# SCH_kea.net
KiCad netlist of a schematic drawn in EasyEDA
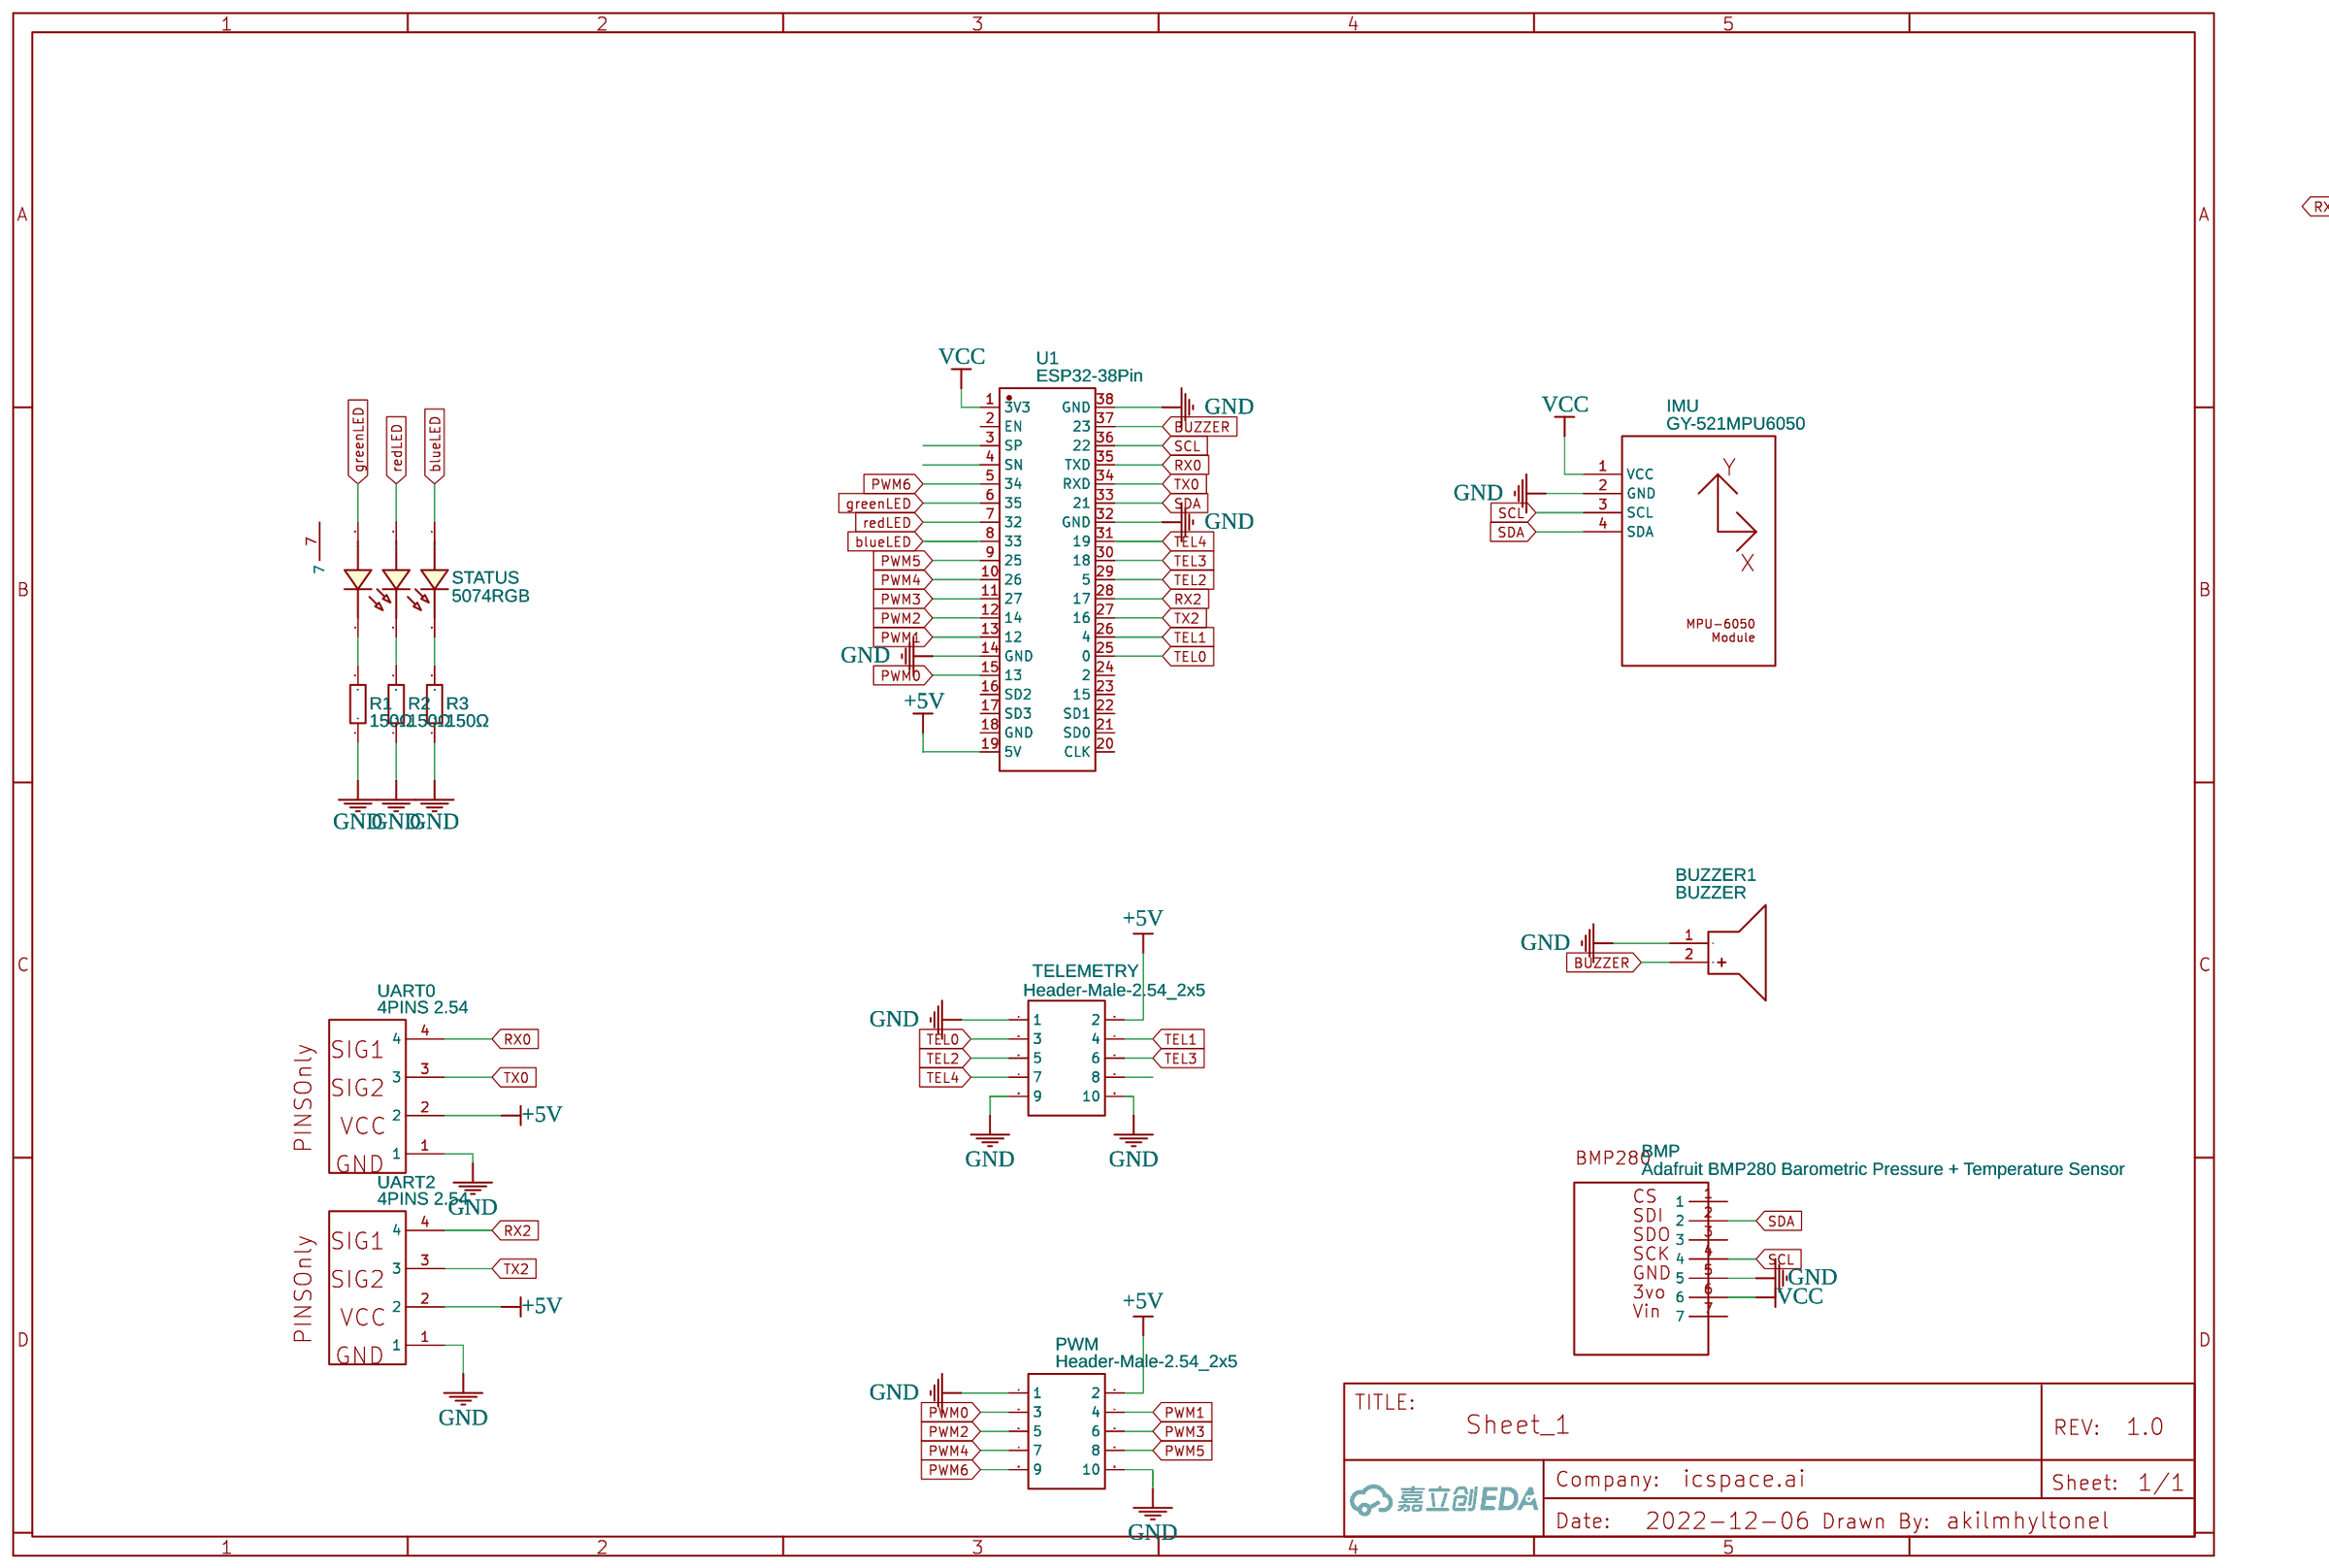
[diagram p0: schematic sheet]

(export (version "E")
  (design (tool "Eeschema 10.0.6"))
  (components
    (comp (ref "BMP")
      (value "Adafruit BMP280 Barometric Pressure + Temperature Sensor")
      (fields (field (name "BOM_Manufacturer Part") "Adafruit"))
      (libsource (lib "") (part "Adafruit BMP280 Barometric Pressure + Temperature Sensor"))
    )
    (comp (ref "BUZZER1")
      (value "BUZZER")
      (fields
        (field (name "BOM_Manufacturer Part") "buzzer")
        (field (name "BOM_Supplier Part") "C9900014030")
      )
      (libsource (lib "") (part "BUZZER"))
    )
    (comp (ref "IMU") (value "GY-521MPU6050") (libsource (lib "") (part "GY-521MPU6050")))
    (comp (ref "PWM")
      (value "Header-Male-2.54_2x5")
      (fields
        (field (name "BOM_Manufacturer Part") "2*5pHeaders  Pins 2.54mm")
        (field (name "BOM_Supplier Part") "C28207")
      )
      (libsource (lib "") (part "Header-Male-2.54_2x5"))
    )
    (comp (ref "R1")
      (value "150Ω")
      (fields
        (field (name "BOM_Manufacturer Part") "AECR0603F160KK9")
        (field (name "BOM_Supplier Part") "C352365")
      )
      (libsource (lib "") (part "AECR0603F160KK9"))
    )
    (comp (ref "R2")
      (value "150Ω")
      (fields
        (field (name "BOM_Manufacturer Part") "AECR0603F160KK9")
        (field (name "BOM_Supplier Part") "C352365")
      )
      (libsource (lib "") (part "AECR0603F160KK9"))
    )
    (comp (ref "R3")
      (value "150Ω")
      (fields
        (field (name "BOM_Manufacturer Part") "AECR0603F160KK9")
        (field (name "BOM_Supplier Part") "C352365")
      )
      (libsource (lib "") (part "AECR0603F160KK9"))
    )
    (comp (ref "STATUS")
      (value "5074RGB")
      (fields (field (name "BOM_Supplier Part") "C9900017134"))
      (libsource (lib "") (part "5074RGB"))
    )
    (comp (ref "TELEMETRY")
      (value "Header-Male-2.54_2x5")
      (fields
        (field (name "BOM_Manufacturer Part") "2*5pHeaders  Pins 2.54mm")
        (field (name "BOM_Supplier Part") "C28207")
      )
      (libsource (lib "") (part "Header-Male-2.54_2x5_1"))
    )
    (comp (ref "U1") (value "ESP32-38Pin") (libsource (lib "") (part "ESP32-38Pin")))
    (comp (ref "UART0") (value "4PINS 2.54") (libsource (lib "") (part "4PINS 2.54")))
    (comp (ref "UART2") (value "4PINS 2.54") (libsource (lib "") (part "4PINS 2.54")))
  )
  (nets
    (net (code "1") (name "+5V") (class "Default")
      (node (ref "PWM") (pin "2") (pinfunction "2_2") (pintype "input"))
      (node (ref "TELEMETRY") (pin "2") (pinfunction "2_2") (pintype "input"))
      (node (ref "U1") (pin "19") (pinfunction "5V_19") (pintype "unspecified"))
      (node (ref "UART0") (pin "2") (pinfunction "2_2") (pintype "unspecified"))
      (node (ref "UART2") (pin "2") (pinfunction "2_2") (pintype "unspecified"))
    )
    (net (code "2") (name "BUZZER") (class "Default")
      (node (ref "BUZZER1") (pin "2") (pinfunction "+_2") (pintype "unspecified"))
      (node (ref "U1") (pin "37") (pinfunction "23_37") (pintype "unspecified"))
    )
    (net (code "3") (name "GND") (class "Default")
      (node (ref "BMP") (pin "5") (pinfunction "5_5") (pintype "unspecified"))
      (node (ref "BUZZER1") (pin "1") (pinfunction "-_1") (pintype "unspecified"))
      (node (ref "IMU") (pin "2") (pinfunction "GND_2") (pintype "unspecified"))
      (node (ref "PWM") (pin "1") (pinfunction "1_1") (pintype "input"))
      (node (ref "PWM") (pin "10") (pinfunction "10_10") (pintype "input"))
      (node (ref "R1") (pin "1") (pinfunction "1_1") (pintype "unspecified"))
      (node (ref "R2") (pin "1") (pinfunction "1_1") (pintype "unspecified"))
      (node (ref "R3") (pin "1") (pinfunction "1_1") (pintype "unspecified"))
      (node (ref "TELEMETRY") (pin "1") (pinfunction "1_1") (pintype "input"))
      (node (ref "TELEMETRY") (pin "10") (pinfunction "10_10") (pintype "input"))
      (node (ref "TELEMETRY") (pin "9") (pinfunction "9_9") (pintype "input"))
      (node (ref "U1") (pin "14") (pinfunction "GND_14") (pintype "unspecified"))
      (node (ref "U1") (pin "32") (pinfunction "GND_32") (pintype "unspecified"))
      (node (ref "U1") (pin "38") (pinfunction "GND_38") (pintype "unspecified"))
      (node (ref "UART0") (pin "1") (pinfunction "1_1") (pintype "unspecified"))
      (node (ref "UART2") (pin "1") (pinfunction "1_1") (pintype "unspecified"))
    )
    (net (code "4") (name "Net-(R1-Pad2)") (class "Default")
      (node (ref "R1") (pin "2") (pinfunction "2_2") (pintype "unspecified"))
      (node (ref "STATUS") (pin "3") (pinfunction "-_3") (pintype "unspecified"))
    )
    (net (code "5") (name "Net-(R2-Pad2)") (class "Default")
      (node (ref "R2") (pin "2") (pinfunction "2_2") (pintype "unspecified"))
      (node (ref "STATUS") (pin "2") (pinfunction "-_2") (pintype "unspecified"))
    )
    (net (code "6") (name "Net-(R3-Pad2)") (class "Default")
      (node (ref "R3") (pin "2") (pinfunction "2_2") (pintype "unspecified"))
      (node (ref "STATUS") (pin "1") (pinfunction "-_1") (pintype "unspecified"))
    )
    (net (code "7") (name "PWM0") (class "Default")
      (node (ref "PWM") (pin "3") (pinfunction "3_3") (pintype "input"))
      (node (ref "U1") (pin "15") (pinfunction "13_15") (pintype "unspecified"))
    )
    (net (code "8") (name "PWM1") (class "Default")
      (node (ref "PWM") (pin "4") (pinfunction "4_4") (pintype "input"))
      (node (ref "U1") (pin "13") (pinfunction "12_13") (pintype "unspecified"))
    )
    (net (code "9") (name "PWM2") (class "Default")
      (node (ref "PWM") (pin "5") (pinfunction "5_5") (pintype "input"))
      (node (ref "U1") (pin "12") (pinfunction "14_12") (pintype "unspecified"))
    )
    (net (code "10") (name "PWM3") (class "Default")
      (node (ref "PWM") (pin "6") (pinfunction "6_6") (pintype "input"))
      (node (ref "U1") (pin "11") (pinfunction "27_11") (pintype "unspecified"))
    )
    (net (code "11") (name "PWM4") (class "Default")
      (node (ref "PWM") (pin "7") (pinfunction "7_7") (pintype "input"))
      (node (ref "U1") (pin "10") (pinfunction "26_10") (pintype "unspecified"))
    )
    (net (code "12") (name "PWM5") (class "Default")
      (node (ref "PWM") (pin "8") (pinfunction "8_8") (pintype "input"))
      (node (ref "U1") (pin "9") (pinfunction "25_9") (pintype "unspecified"))
    )
    (net (code "13") (name "PWM6") (class "Default")
      (node (ref "PWM") (pin "9") (pinfunction "9_9") (pintype "input"))
      (node (ref "U1") (pin "5") (pinfunction "34_5") (pintype "unspecified"))
    )
    (net (code "14") (name "RX0") (class "Default")
      (node (ref "U1") (pin "35") (pinfunction "TXD_35") (pintype "unspecified"))
      (node (ref "UART0") (pin "4") (pinfunction "4_4") (pintype "unspecified"))
    )
    (net (code "15") (name "RX2") (class "Default")
      (node (ref "U1") (pin "28") (pinfunction "17_28") (pintype "unspecified"))
      (node (ref "UART2") (pin "4") (pinfunction "4_4") (pintype "unspecified"))
    )
    (net (code "16") (name "SCL") (class "Default")
      (node (ref "BMP") (pin "4") (pinfunction "4_4") (pintype "unspecified"))
      (node (ref "IMU") (pin "3") (pinfunction "SCL_3") (pintype "unspecified"))
      (node (ref "U1") (pin "36") (pinfunction "22_36") (pintype "unspecified"))
    )
    (net (code "17") (name "SDA") (class "Default")
      (node (ref "BMP") (pin "2") (pinfunction "2_2") (pintype "unspecified"))
      (node (ref "IMU") (pin "4") (pinfunction "SDA_4") (pintype "unspecified"))
      (node (ref "U1") (pin "33") (pinfunction "21_33") (pintype "unspecified"))
    )
    (net (code "18") (name "TEL0") (class "Default")
      (node (ref "TELEMETRY") (pin "3") (pinfunction "3_3") (pintype "input"))
      (node (ref "U1") (pin "25") (pinfunction "0_25") (pintype "unspecified"))
    )
    (net (code "19") (name "TEL1") (class "Default")
      (node (ref "TELEMETRY") (pin "4") (pinfunction "4_4") (pintype "input"))
      (node (ref "U1") (pin "26") (pinfunction "4_26") (pintype "unspecified"))
    )
    (net (code "20") (name "TEL2") (class "Default")
      (node (ref "TELEMETRY") (pin "5") (pinfunction "5_5") (pintype "input"))
      (node (ref "U1") (pin "29") (pinfunction "5_29") (pintype "unspecified"))
    )
    (net (code "21") (name "TEL3") (class "Default")
      (node (ref "TELEMETRY") (pin "6") (pinfunction "6_6") (pintype "input"))
      (node (ref "U1") (pin "30") (pinfunction "18_30") (pintype "unspecified"))
    )
    (net (code "22") (name "TEL4") (class "Default")
      (node (ref "TELEMETRY") (pin "7") (pinfunction "7_7") (pintype "input"))
      (node (ref "U1") (pin "31") (pinfunction "19_31") (pintype "unspecified"))
    )
    (net (code "23") (name "TX0") (class "Default")
      (node (ref "U1") (pin "34") (pinfunction "RXD_34") (pintype "unspecified"))
      (node (ref "UART0") (pin "3") (pinfunction "3_3") (pintype "unspecified"))
    )
    (net (code "24") (name "TX2") (class "Default")
      (node (ref "U1") (pin "27") (pinfunction "16_27") (pintype "unspecified"))
      (node (ref "UART2") (pin "3") (pinfunction "3_3") (pintype "unspecified"))
    )
    (net (code "25") (name "VCC") (class "Default")
      (node (ref "BMP") (pin "6") (pinfunction "6_6") (pintype "unspecified"))
      (node (ref "IMU") (pin "1") (pinfunction "VCC_1") (pintype "unspecified"))
      (node (ref "U1") (pin "1") (pinfunction "3V3_1") (pintype "unspecified"))
    )
    (net (code "26") (name "blueLED") (class "Default")
      (node (ref "STATUS") (pin "4") (pinfunction "+_4") (pintype "unspecified"))
      (node (ref "U1") (pin "8") (pinfunction "33_8") (pintype "unspecified"))
    )
    (net (code "27") (name "greenLED") (class "Default")
      (node (ref "STATUS") (pin "6") (pinfunction "+_6") (pintype "unspecified"))
      (node (ref "U1") (pin "6") (pinfunction "35_6") (pintype "unspecified"))
    )
    (net (code "28") (name "redLED") (class "Default")
      (node (ref "STATUS") (pin "5") (pinfunction "+_5") (pintype "unspecified"))
      (node (ref "U1") (pin "7") (pinfunction "32_7") (pintype "unspecified"))
    )
    (net (code "29") (name "unconnected-(BMP-Pad1)") (class "Default")
      (node (ref "BMP") (pin "1") (pinfunction "1_1") (pintype "unspecified"))
    )
    (net (code "30") (name "unconnected-(BMP-Pad3)") (class "Default")
      (node (ref "BMP") (pin "3") (pinfunction "3_3") (pintype "unspecified"))
    )
    (net (code "31") (name "unconnected-(BMP-Pad7)") (class "Default")
      (node (ref "BMP") (pin "7") (pinfunction "7_7") (pintype "unspecified"))
    )
    (net (code "32") (name "unconnected-(STATUS-Pad7)") (class "Default")
      (node (ref "STATUS") (pin "7") (pinfunction "7_7") (pintype "unspecified"))
    )
    (net (code "33") (name "unconnected-(TELEMETRY-Pad8)") (class "Default")
      (node (ref "TELEMETRY") (pin "8") (pinfunction "8_8") (pintype "input"))
    )
    (net (code "34") (name "unconnected-(U1-2-Pad24)") (class "Default")
      (node (ref "U1") (pin "24") (pinfunction "2_24") (pintype "unspecified"))
    )
    (net (code "35") (name "unconnected-(U1-15-Pad23)") (class "Default")
      (node (ref "U1") (pin "23") (pinfunction "15_23") (pintype "unspecified"))
    )
    (net (code "36") (name "unconnected-(U1-CLK-Pad20)") (class "Default")
      (node (ref "U1") (pin "20") (pinfunction "CLK_20") (pintype "unspecified"))
    )
    (net (code "37") (name "unconnected-(U1-EN-Pad2)") (class "Default")
      (node (ref "U1") (pin "2") (pinfunction "EN_2") (pintype "unspecified"))
    )
    (net (code "38") (name "unconnected-(U1-GND-Pad18)") (class "Default")
      (node (ref "U1") (pin "18") (pinfunction "GND_18") (pintype "unspecified"))
    )
    (net (code "39") (name "unconnected-(U1-SD0-Pad21)") (class "Default")
      (node (ref "U1") (pin "21") (pinfunction "SD0_21") (pintype "unspecified"))
    )
    (net (code "40") (name "unconnected-(U1-SD1-Pad22)") (class "Default")
      (node (ref "U1") (pin "22") (pinfunction "SD1_22") (pintype "unspecified"))
    )
    (net (code "41") (name "unconnected-(U1-SD2-Pad16)") (class "Default")
      (node (ref "U1") (pin "16") (pinfunction "SD2_16") (pintype "unspecified"))
    )
    (net (code "42") (name "unconnected-(U1-SD3-Pad17)") (class "Default")
      (node (ref "U1") (pin "17") (pinfunction "SD3_17") (pintype "unspecified"))
    )
    (net (code "43") (name "unconnected-(U1-SN-Pad4)") (class "Default")
      (node (ref "U1") (pin "4") (pinfunction "SN_4") (pintype "unspecified"))
    )
    (net (code "44") (name "unconnected-(U1-SP-Pad3)") (class "Default")
      (node (ref "U1") (pin "3") (pinfunction "SP_3") (pintype "unspecified"))
    )
  )
)
